# Qwiic_MLX90393_Magnetometer.net
KiCad netlist of a schematic drawn in EAGLE
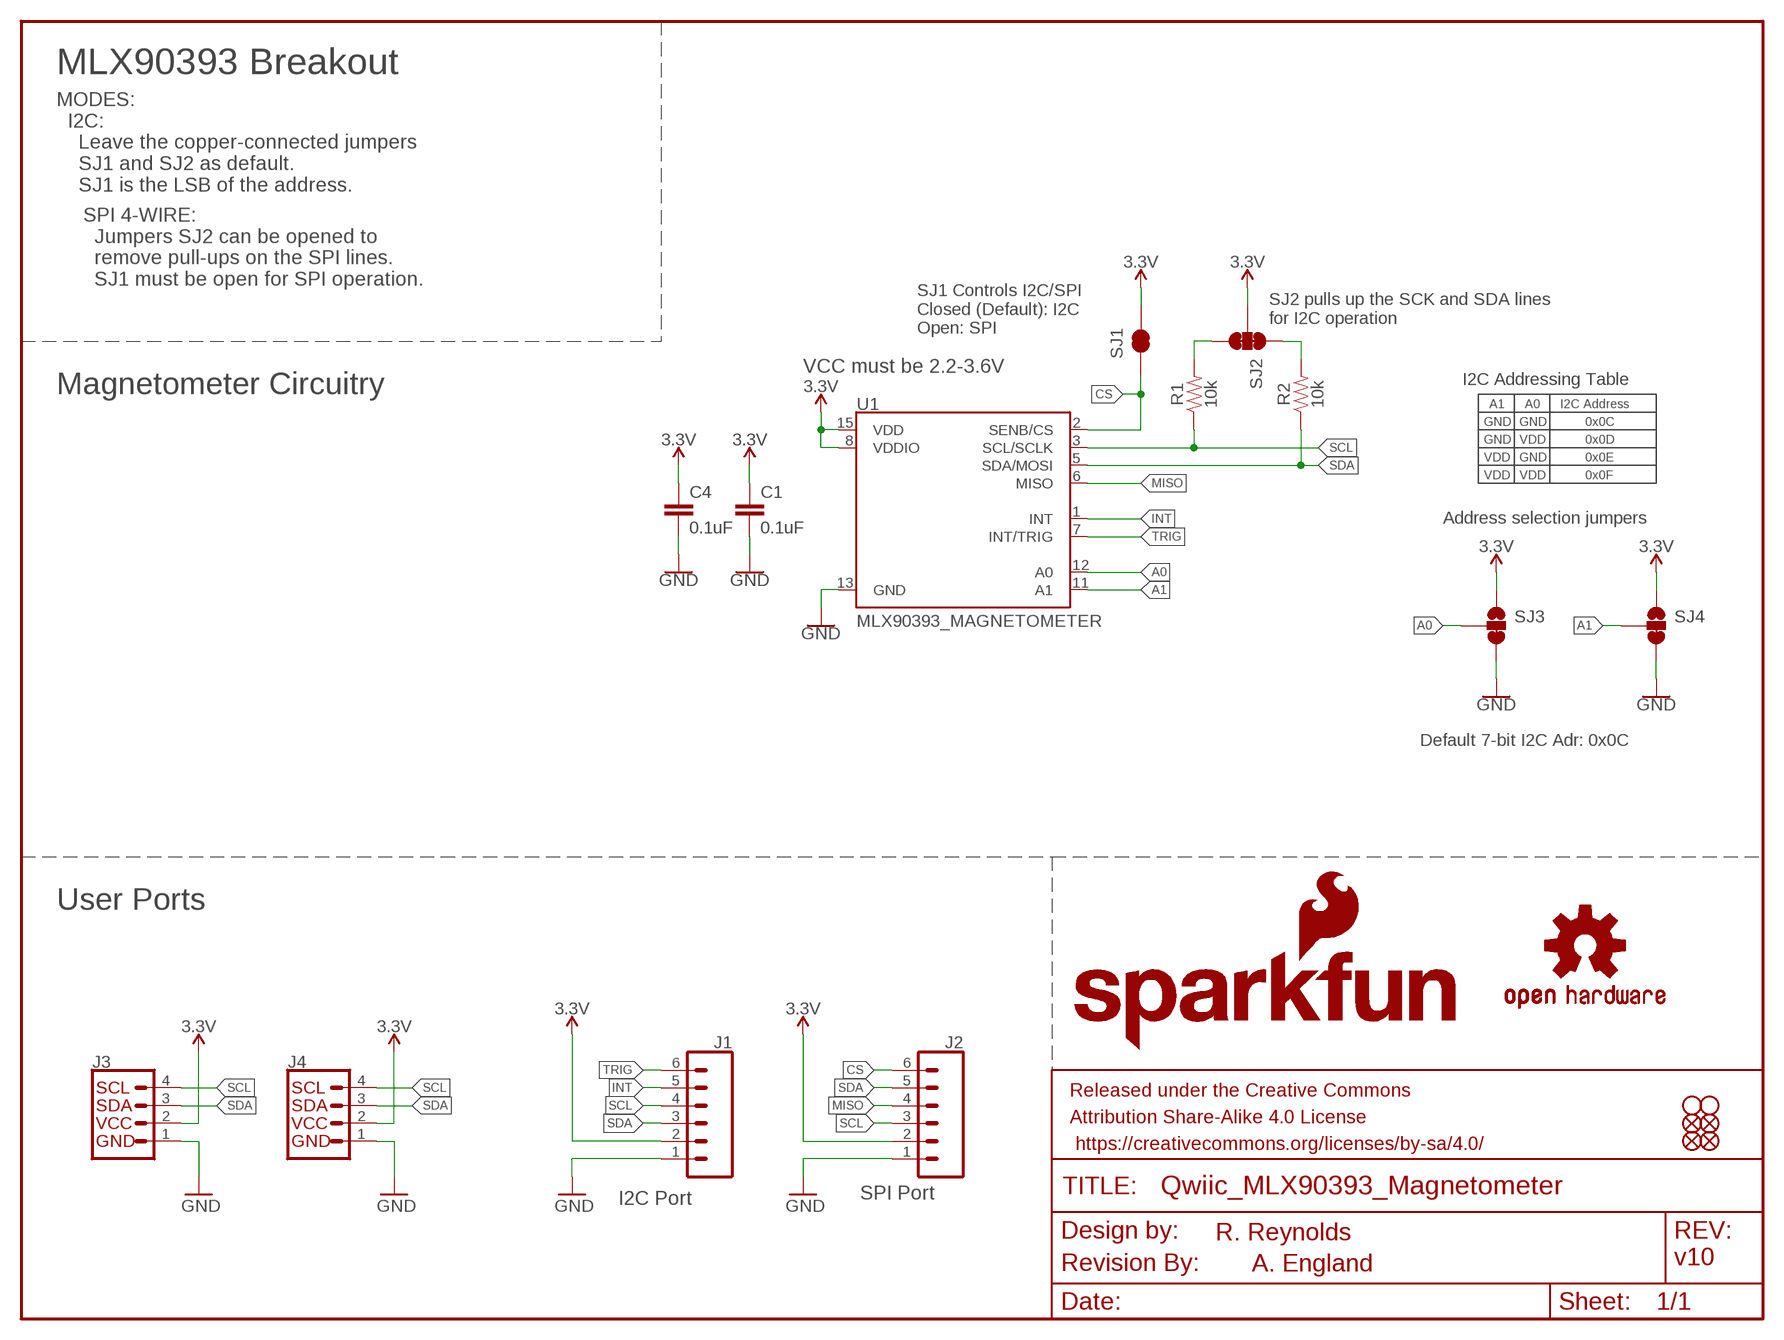
[diagram p0: schematic, sheet 1]

(export (version "E")
  (design (tool "Eeschema 10.0.6"))
  (components
    (comp (ref "C1")
      (value "0.1uF")
      (footprint "eagle-import:0603")
      (libsource (lib "eagle-import") (part "0.1UF-0603-25V-(+80/-20%)"))
    )
    (comp (ref "C4")
      (value "0.1uF")
      (footprint "eagle-import:0603")
      (libsource (lib "eagle-import") (part "0.1UF-0603-25V-(+80/-20%)"))
    )
    (comp (ref "FD1")
      (value "FIDUCIALUFIDUCIAL")
      (footprint "eagle-import:FIDUCIAL-MICRO")
      (libsource (lib "eagle-import") (part "FIDUCIALUFIDUCIAL"))
    )
    (comp (ref "FD2")
      (value "FIDUCIALUFIDUCIAL")
      (footprint "eagle-import:FIDUCIAL-MICRO")
      (libsource (lib "eagle-import") (part "FIDUCIALUFIDUCIAL"))
    )
    (comp (ref "FD3")
      (value "FIDUCIALUFIDUCIAL")
      (footprint "eagle-import:FIDUCIAL-MICRO")
      (libsource (lib "eagle-import") (part "FIDUCIALUFIDUCIAL"))
    )
    (comp (ref "FD4")
      (value "FIDUCIALUFIDUCIAL")
      (footprint "eagle-import:FIDUCIAL-MICRO")
      (libsource (lib "eagle-import") (part "FIDUCIALUFIDUCIAL"))
    )
    (comp (ref "FRAME2")
      (value "FRAME-LETTER")
      (footprint "eagle-import:CREATIVE_COMMONS")
      (libsource (lib "eagle-import") (part "FRAME-LETTER"))
    )
    (comp (ref "J1")
      (value "CONN_06NO_SILK_FEMALE_PTH")
      (footprint "eagle-import:1X06_NO_SILK")
      (libsource (lib "eagle-import") (part "CONN_06NO_SILK_FEMALE_PTH"))
    )
    (comp (ref "J2")
      (value "CONN_06NO_SILK_FEMALE_PTH")
      (footprint "eagle-import:1X06_NO_SILK")
      (libsource (lib "eagle-import") (part "CONN_06NO_SILK_FEMALE_PTH"))
    )
    (comp (ref "J3")
      (value "QWIIC_CONNECTORJS-1MM")
      (footprint "eagle-import:1X04_1MM_RA")
      (libsource (lib "eagle-import") (part "QWIIC_CONNECTORJS-1MM"))
    )
    (comp (ref "J4")
      (value "QWIIC_CONNECTORJS-1MM")
      (footprint "eagle-import:1X04_1MM_RA")
      (libsource (lib "eagle-import") (part "QWIIC_CONNECTORJS-1MM"))
    )
    (comp (ref "JP3")
      (value "STAND-OFF")
      (footprint "eagle-import:STAND-OFF")
      (libsource (lib "eagle-import") (part "STAND-OFF"))
    )
    (comp (ref "JP4")
      (value "STAND-OFF")
      (footprint "eagle-import:STAND-OFF")
      (libsource (lib "eagle-import") (part "STAND-OFF"))
    )
    (comp (ref "LOGO1")
      (value "SFE_LOGO_NAME_FLAME.1_INCH")
      (footprint "eagle-import:SFE_LOGO_NAME_FLAME_.1")
      (libsource (lib "eagle-import") (part "SFE_LOGO_NAME_FLAME.1_INCH"))
    )
    (comp (ref "LOGO2")
      (value "SFE_LOGO_FLAME.1_INCH")
      (footprint "eagle-import:SFE_LOGO_FLAME_.1")
      (libsource (lib "eagle-import") (part "SFE_LOGO_FLAME.1_INCH"))
    )
    (comp (ref "LOGO3")
      (value "REVISION")
      (footprint "eagle-import:REVISION")
      (libsource (lib "eagle-import") (part "REVISION"))
    )
    (comp (ref "R1")
      (value "10k")
      (footprint "eagle-import:0603")
      (libsource (lib "eagle-import") (part "10KOHM-0603-1/10W-1%"))
    )
    (comp (ref "R2")
      (value "10k")
      (footprint "eagle-import:0603")
      (libsource (lib "eagle-import") (part "10KOHM-0603-1/10W-1%"))
    )
    (comp (ref "SJ1")
      (value "JUMPER-SMT_2_NC_TRACE_SILK")
      (footprint "eagle-import:SMT-JUMPER_2_NC_TRACE_SILK")
      (libsource (lib "eagle-import") (part "JUMPER-SMT_2_NC_TRACE_SILK"))
    )
    (comp (ref "SJ2")
      (value "JUMPER-PAD-3-NC_BY_TRACE")
      (footprint "eagle-import:PAD-JUMPER-3-3OF3_NC_BY_TRACE_YES_SILK_FULL_BOX")
      (libsource (lib "eagle-import") (part "JUMPER-PAD-3-NC_BY_TRACE"))
    )
    (comp (ref "SJ3")
      (value "JUMPER-SMT_3_1-NC_TRACE_SILK")
      (footprint "eagle-import:SMT-JUMPER_3_1-NC_TRACE_SILK")
      (libsource (lib "eagle-import") (part "JUMPER-SMT_3_1-NC_TRACE_SILK"))
    )
    (comp (ref "SJ4")
      (value "JUMPER-SMT_3_1-NC_TRACE_SILK")
      (footprint "eagle-import:SMT-JUMPER_3_1-NC_TRACE_SILK")
      (libsource (lib "eagle-import") (part "JUMPER-SMT_3_1-NC_TRACE_SILK"))
    )
    (comp (ref "U$1")
      (value "OSHW-LOGOS")
      (footprint "eagle-import:OSHW-LOGO-S")
      (libsource (lib "eagle-import") (part "OSHW-LOGOS"))
    )
    (comp (ref "U1")
      (value "MLX90393_MAGNETOMETER")
      (footprint "eagle-import:QFN-16_WITH_AXIES")
      (libsource (lib "eagle-import") (part "MLX90393_MAGNETOMETER"))
    )
  )
  (nets
    (net (code "1") (name "3.3V") (class "Default")
      (node (ref "C1") (pin "1") (pinfunction "1_1") (pintype "passive"))
      (node (ref "C4") (pin "1") (pinfunction "1_1") (pintype "passive"))
      (node (ref "J1") (pin "2") (pinfunction "2_2") (pintype "passive"))
      (node (ref "J2") (pin "2") (pinfunction "2_2") (pintype "passive"))
      (node (ref "J3") (pin "2") (pinfunction "2_2") (pintype "power_in"))
      (node (ref "J4") (pin "2") (pinfunction "2_2") (pintype "power_in"))
      (node (ref "SJ1") (pin "2") (pinfunction "2_2") (pintype "passive"))
      (node (ref "SJ2") (pin "2") (pinfunction "2_2") (pintype "passive"))
      (node (ref "SJ3") (pin "1") (pinfunction "1_1") (pintype "passive"))
      (node (ref "SJ4") (pin "1") (pinfunction "1_1") (pintype "passive"))
      (node (ref "U1") (pin "15") (pinfunction "VDD_15") (pintype "bidirectional"))
      (node (ref "U1") (pin "8") (pinfunction "VDDIO_8") (pintype "bidirectional"))
    )
    (net (code "2") (name "A0") (class "Default")
      (node (ref "SJ3") (pin "2") (pinfunction "2_2") (pintype "passive"))
      (node (ref "U1") (pin "12") (pinfunction "A0_12") (pintype "bidirectional"))
    )
    (net (code "3") (name "A1") (class "Default")
      (node (ref "SJ4") (pin "2") (pinfunction "2_2") (pintype "passive"))
      (node (ref "U1") (pin "11") (pinfunction "A1_11") (pintype "bidirectional"))
    )
    (net (code "4") (name "CS") (class "Default")
      (node (ref "J2") (pin "6") (pinfunction "6_6") (pintype "passive"))
      (node (ref "SJ1") (pin "1") (pinfunction "1_1") (pintype "passive"))
      (node (ref "U1") (pin "2") (pinfunction "SENB/CS_2") (pintype "bidirectional"))
    )
    (net (code "5") (name "GND") (class "Default")
      (node (ref "C1") (pin "2") (pinfunction "2_2") (pintype "passive"))
      (node (ref "C4") (pin "2") (pinfunction "2_2") (pintype "passive"))
      (node (ref "J1") (pin "1") (pinfunction "1_1") (pintype "passive"))
      (node (ref "J2") (pin "1") (pinfunction "1_1") (pintype "passive"))
      (node (ref "J3") (pin "1") (pinfunction "1_1") (pintype "power_in"))
      (node (ref "J4") (pin "1") (pinfunction "1_1") (pintype "power_in"))
      (node (ref "SJ3") (pin "3") (pinfunction "3_3") (pintype "passive"))
      (node (ref "SJ4") (pin "3") (pinfunction "3_3") (pintype "passive"))
      (node (ref "U1") (pin "13") (pinfunction "GND_13") (pintype "bidirectional"))
    )
    (net (code "6") (name "INT") (class "Default")
      (node (ref "J1") (pin "5") (pinfunction "5_5") (pintype "passive"))
      (node (ref "U1") (pin "1") (pinfunction "INT_1") (pintype "bidirectional"))
    )
    (net (code "7") (name "MISO") (class "Default")
      (node (ref "J2") (pin "4") (pinfunction "4_4") (pintype "passive"))
      (node (ref "U1") (pin "6") (pinfunction "MISO_6") (pintype "bidirectional"))
    )
    (net (code "8") (name "Net-(R1-Pad2)") (class "Default")
      (node (ref "R1") (pin "2") (pinfunction "2_2") (pintype "passive"))
      (node (ref "SJ2") (pin "3") (pinfunction "3_3") (pintype "passive"))
    )
    (net (code "9") (name "Net-(R2-Pad2)") (class "Default")
      (node (ref "R2") (pin "2") (pinfunction "2_2") (pintype "passive"))
      (node (ref "SJ2") (pin "1") (pinfunction "1_1") (pintype "passive"))
    )
    (net (code "10") (name "SCL") (class "Default")
      (node (ref "J1") (pin "4") (pinfunction "4_4") (pintype "passive"))
      (node (ref "J2") (pin "3") (pinfunction "3_3") (pintype "passive"))
      (node (ref "J3") (pin "4") (pinfunction "4_4") (pintype "passive"))
      (node (ref "J4") (pin "4") (pinfunction "4_4") (pintype "passive"))
      (node (ref "R1") (pin "1") (pinfunction "1_1") (pintype "passive"))
      (node (ref "U1") (pin "3") (pinfunction "SCL/SCLK_3") (pintype "bidirectional"))
    )
    (net (code "11") (name "SDA") (class "Default")
      (node (ref "J1") (pin "3") (pinfunction "3_3") (pintype "passive"))
      (node (ref "J2") (pin "5") (pinfunction "5_5") (pintype "passive"))
      (node (ref "J3") (pin "3") (pinfunction "3_3") (pintype "passive"))
      (node (ref "J4") (pin "3") (pinfunction "3_3") (pintype "passive"))
      (node (ref "R2") (pin "1") (pinfunction "1_1") (pintype "passive"))
      (node (ref "U1") (pin "5") (pinfunction "SDA/MOSI_5") (pintype "bidirectional"))
    )
    (net (code "12") (name "TRIG") (class "Default")
      (node (ref "J1") (pin "6") (pinfunction "6_6") (pintype "passive"))
      (node (ref "U1") (pin "7") (pinfunction "INT/TRIG_7") (pintype "bidirectional"))
    )
  )
)
